# STM32P48.net
KiCad netlist of a schematic drawn in Altium Designer
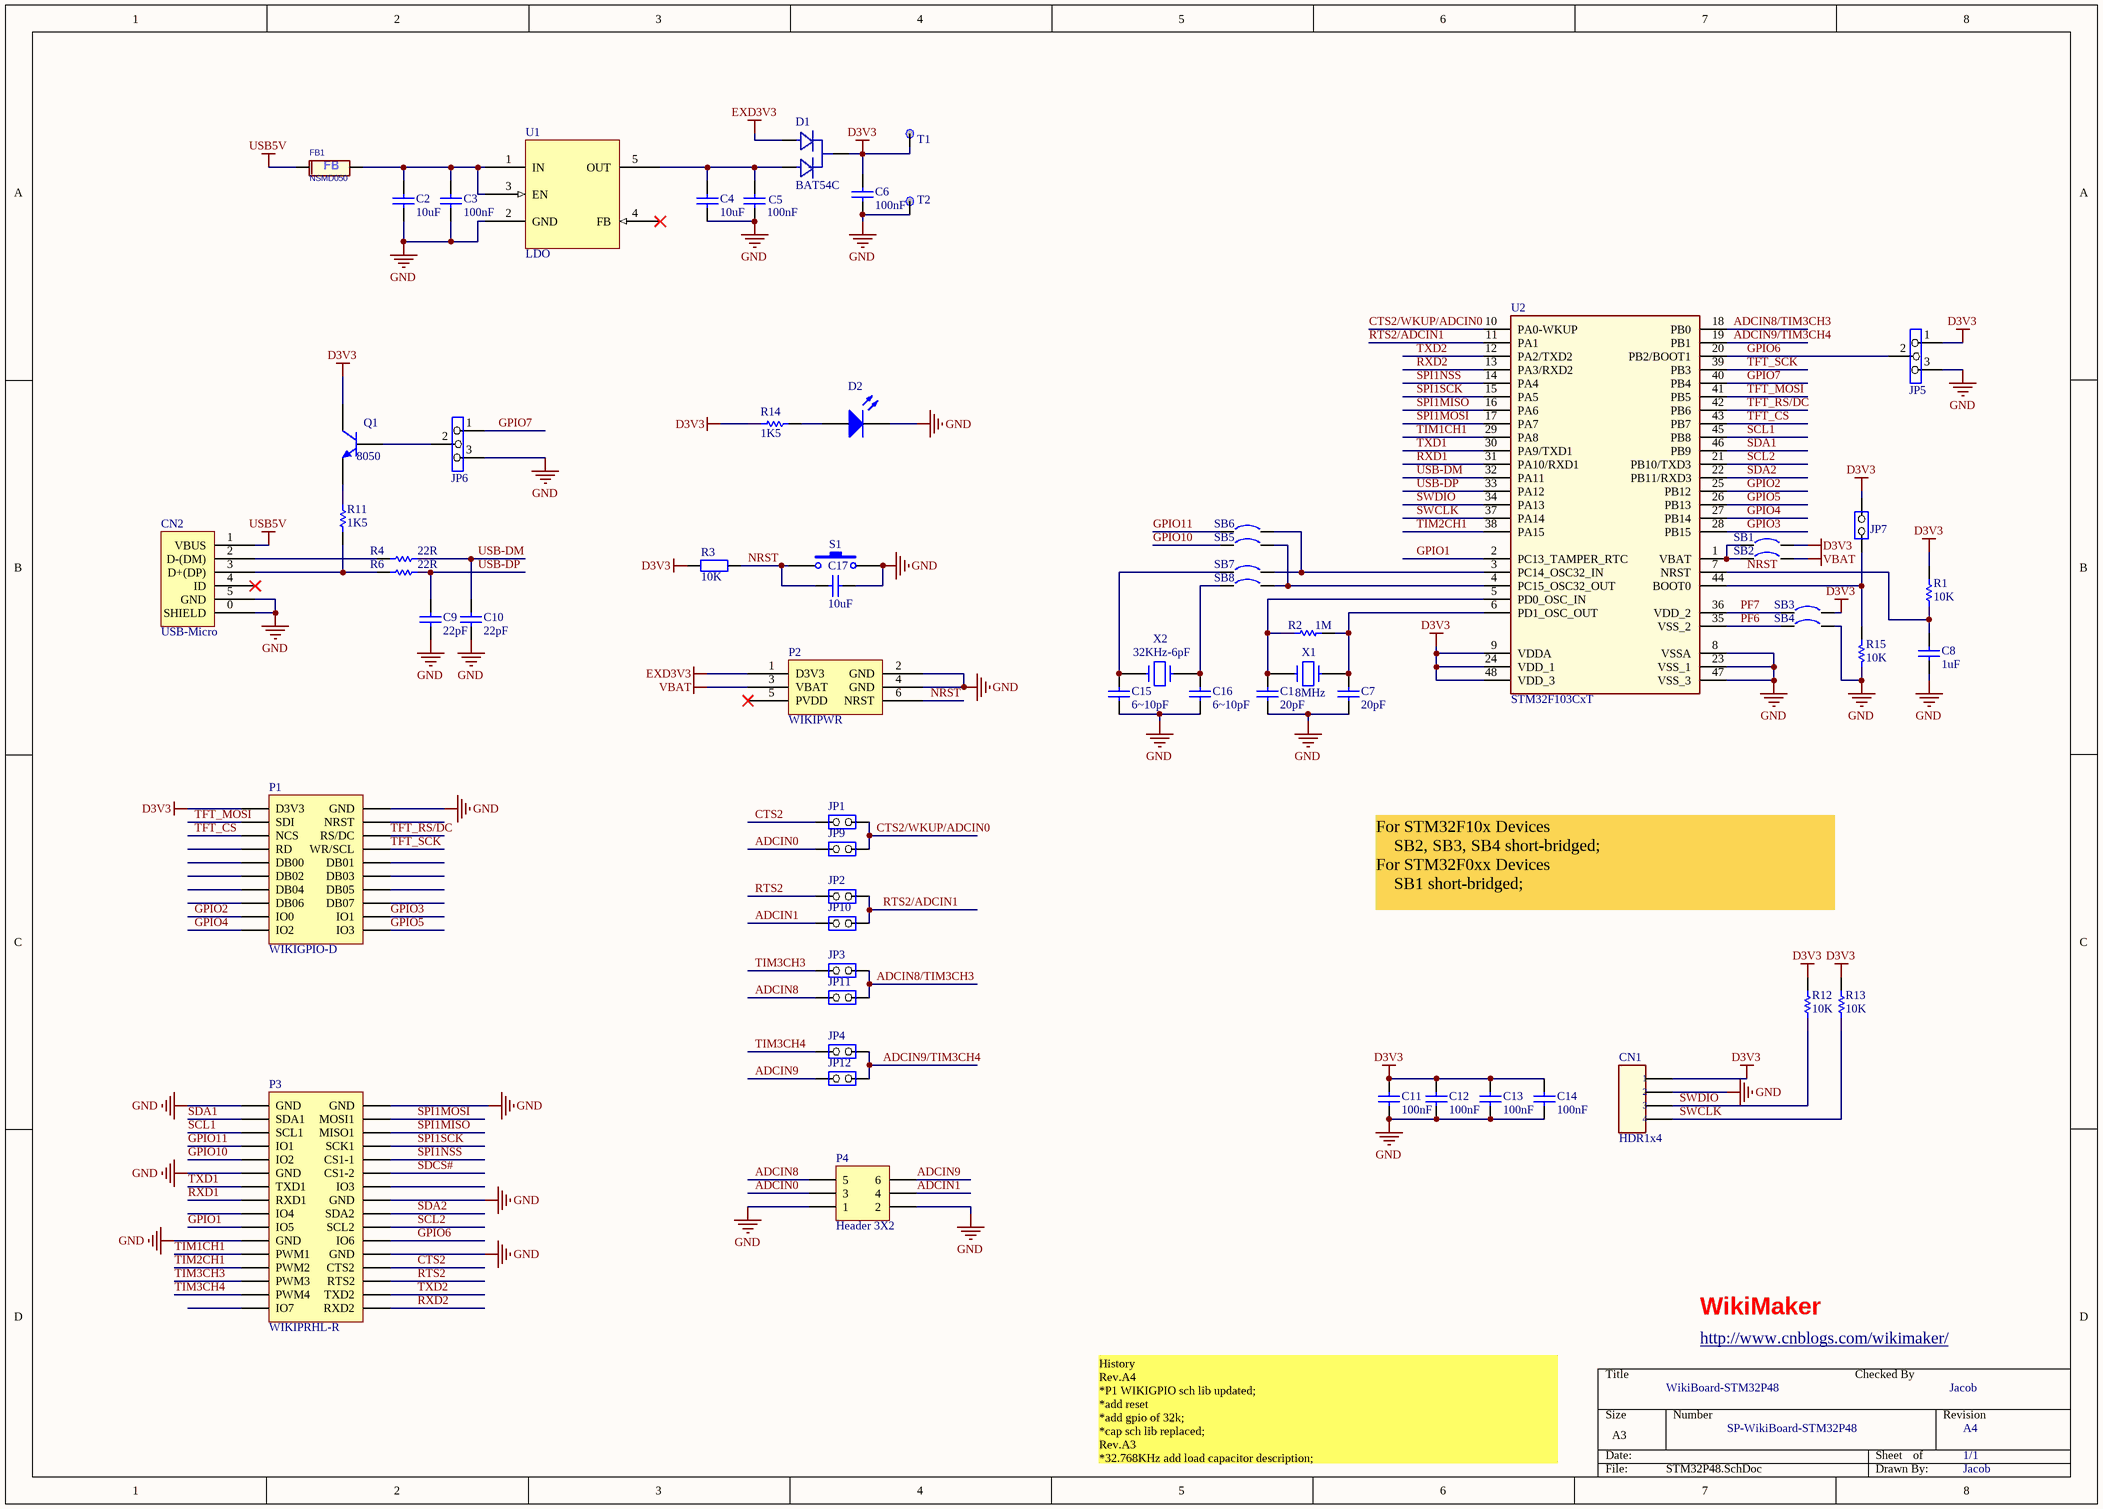
[diagram p0: STM32P48.SchDoc]

(export (version "E")
  (design (tool "Eeschema 10.0.6"))
  (components
    (comp (ref "C1")
      (value "20pF")
      (footprint "C0603L")
      (description "Capacitor")
      (fields (field (name "PUBLISHER") "Altium Limited"))
      (libsource (lib "Miscellaneous Devices") (part "Cap"))
    )
    (comp (ref "C2")
      (value "10uF")
      (footprint "C0805")
      (description "Capacitor")
      (fields (field (name "PUBLISHER") "Altium Limited"))
      (libsource (lib "Miscellaneous Devices") (part "Cap"))
    )
    (comp (ref "C3")
      (value "100nF")
      (footprint "C0603L")
      (description "Capacitor")
      (fields (field (name "PUBLISHER") "Altium Limited"))
      (libsource (lib "Miscellaneous Devices") (part "Cap"))
    )
    (comp (ref "C4")
      (value "10uF")
      (footprint "C0805")
      (description "Capacitor")
      (fields (field (name "PUBLISHER") "Altium Limited"))
      (libsource (lib "Miscellaneous Devices") (part "Cap"))
    )
    (comp (ref "C5")
      (value "100nF")
      (footprint "C0603L")
      (description "Capacitor")
      (fields (field (name "PUBLISHER") "Altium Limited"))
      (libsource (lib "Miscellaneous Devices") (part "Cap"))
    )
    (comp (ref "C6")
      (value "100nF")
      (footprint "C0603L")
      (description "Capacitor")
      (fields (field (name "PUBLISHER") "Altium Limited"))
      (libsource (lib "Miscellaneous Devices") (part "Cap"))
    )
    (comp (ref "C7")
      (value "20pF")
      (footprint "C0603L")
      (description "Capacitor")
      (fields (field (name "PUBLISHER") "Altium Limited"))
      (libsource (lib "Miscellaneous Devices") (part "Cap"))
    )
    (comp (ref "C8")
      (value "1uF")
      (footprint "C0603L")
      (description "Capacitor")
      (fields (field (name "PUBLISHER") "Altium Limited"))
      (libsource (lib "Miscellaneous Devices") (part "Cap"))
    )
    (comp (ref "C9")
      (value "22pF")
      (footprint "C0603L")
      (description "Capacitor")
      (fields (field (name "PUBLISHER") "Altium Limited"))
      (libsource (lib "Miscellaneous Devices") (part "Cap"))
    )
    (comp (ref "C10")
      (value "22pF")
      (footprint "C0603L")
      (description "Capacitor")
      (fields (field (name "PUBLISHER") "Altium Limited"))
      (libsource (lib "Miscellaneous Devices") (part "Cap"))
    )
    (comp (ref "C11")
      (value "100nF")
      (footprint "C0603L")
      (description "Capacitor")
      (fields (field (name "PUBLISHER") "Altium Limited"))
      (libsource (lib "Miscellaneous Devices") (part "Cap"))
    )
    (comp (ref "C12")
      (value "100nF")
      (footprint "C0603L")
      (description "Capacitor")
      (fields (field (name "PUBLISHER") "Altium Limited"))
      (libsource (lib "Miscellaneous Devices") (part "Cap"))
    )
    (comp (ref "C13")
      (value "100nF")
      (footprint "C0603L")
      (description "Capacitor")
      (fields (field (name "PUBLISHER") "Altium Limited"))
      (libsource (lib "Miscellaneous Devices") (part "Cap"))
    )
    (comp (ref "C14")
      (value "100nF")
      (footprint "C0603L")
      (description "Capacitor")
      (fields (field (name "PUBLISHER") "Altium Limited"))
      (libsource (lib "Miscellaneous Devices") (part "Cap"))
    )
    (comp (ref "C15")
      (value "6~10pF")
      (footprint "C0603L")
      (description "Capacitor")
      (fields (field (name "PUBLISHER") "Altium Limited"))
      (libsource (lib "Miscellaneous Devices") (part "Cap"))
    )
    (comp (ref "C16")
      (value "6~10pF")
      (footprint "C0603L")
      (description "Capacitor")
      (fields (field (name "PUBLISHER") "Altium Limited"))
      (libsource (lib "Miscellaneous Devices") (part "Cap"))
    )
    (comp (ref "C17")
      (value "10uF")
      (footprint "C0603L")
      (description "Capacitor")
      (fields (field (name "PUBLISHER") "Altium Limited"))
      (libsource (lib "Miscellaneous Devices") (part "Cap"))
    )
    (comp (ref "CN1") (value "HDR1x4") (footprint "HDR1x4") (libsource (lib "Mylib") (part "CON4")))
    (comp (ref "CN2")
      (value "USB-Micro")
      (footprint "USB-MICRO-Lite")
      (libsource (lib "Connector") (part "USB-Micro"))
    )
    (comp (ref "D1")
      (value "BAT54C")
      (footprint "BAT54C")
      (description "DOUBLE SHOTTKEY DIODES")
      (libsource (lib "Misc") (part "BAT54C"))
    )
    (comp (ref "D2")
      (value "LED1")
      (footprint "0603PN")
      (description "Typical RED GaAs LED")
      (fields (field (name "PUBLISHER") "Altium Limited"))
      (libsource (lib "Misc") (part "LED1"))
    )
    (comp (ref "FB1")
      (value "NSMD050")
      (footprint "R1206")
      (description "Ferrite Beads Inductors Impedance:120Ω±25% Rated Current:1500mA DC Resistance:0.095Ω")
      (fields
        (field (name "MANUFACTURER") "muRata")
        (field (name "MANUFACTURER PART NUMBER") "BLM15EG121SN1")
      )
      (libsource (lib "Mylib") (part "FB"))
    )
    (comp (ref "JP1")
      (value "Jumper2-2")
      (footprint "HDR1X2/2.00MM")
      (description "Jumper2")
      (libsource (lib "Misc") (part "Jumper2-2"))
    )
    (comp (ref "JP2")
      (value "Jumper2-2")
      (footprint "HDR1X2/2.00MM")
      (description "Jumper2")
      (libsource (lib "Misc") (part "Jumper2-2"))
    )
    (comp (ref "JP3")
      (value "Jumper2-2")
      (footprint "HDR1X2/2.00MM")
      (description "Jumper2")
      (libsource (lib "Misc") (part "Jumper2-2"))
    )
    (comp (ref "JP4")
      (value "Jumper2-2")
      (footprint "HDR1X2/2.00MM")
      (description "Jumper2")
      (libsource (lib "Misc") (part "Jumper2-2"))
    )
    (comp (ref "JP5") (value "Jumper3") (footprint "HDR1X3/2.00mm") (libsource (lib "Misc") (part "Jumper3")))
    (comp (ref "JP6") (value "Jumper3") (footprint "HDR1X3/2.00mm") (libsource (lib "Misc") (part "Jumper3")))
    (comp (ref "JP7")
      (value "Jumper2-2")
      (footprint "HDR1X2/2.00MM")
      (description "Jumper2")
      (libsource (lib "Misc") (part "Jumper2-2"))
    )
    (comp (ref "JP9")
      (value "Jumper2-2")
      (footprint "HDR1X2/2.00MM")
      (description "Jumper2")
      (libsource (lib "Misc") (part "Jumper2-2"))
    )
    (comp (ref "JP10")
      (value "Jumper2-2")
      (footprint "HDR1X2/2.00MM")
      (description "Jumper2")
      (libsource (lib "Misc") (part "Jumper2-2"))
    )
    (comp (ref "JP11")
      (value "Jumper2-2")
      (footprint "HDR1X2/2.00MM")
      (description "Jumper2")
      (libsource (lib "Misc") (part "Jumper2-2"))
    )
    (comp (ref "JP12")
      (value "Jumper2-2")
      (footprint "HDR1X2/2.00MM")
      (description "Jumper2")
      (libsource (lib "Misc") (part "Jumper2-2"))
    )
    (comp (ref "P1")
      (value "WIKIGPIO-D")
      (footprint "WIKIGPIO-U")
      (description "Header, 9-Pin, Dual row")
      (fields (field (name "PUBLISHER") "Altium Limited"))
      (libsource (lib "Connector") (part "WIKIGPIO-D"))
    )
    (comp (ref "P2")
      (value "WIKIPWR")
      (footprint "WIKIPWR")
      (description "PWR HDR")
      (libsource (lib "Connector") (part "WIKIPWR"))
    )
    (comp (ref "P3")
      (value "WIKIPRHL-R")
      (footprint "HDR2X16-WIKIPRHL-R")
      (description "Header, 16-Pin, Dual row")
      (fields (field (name "PUBLISHER") "Altium Limited"))
      (libsource (lib "Connector") (part "WIKIPRHL-R"))
    )
    (comp (ref "P4")
      (value "Header 3X2")
      (footprint "HDR2X3/2.54MM")
      (description "Header, 3-Pin, Dual row")
      (fields (field (name "PUBLISHER") "Altium Limited"))
      (libsource (lib "Miscellaneous Connectors") (part "Header 3X2"))
    )
    (comp (ref "Q1")
      (value "8050")
      (footprint "SOT23-3L(123)")
      (description "NPN General Purpose Amplifier")
      (fields (field (name "PUBLISHER") "Altium Limited"))
      (libsource (lib "Misc") (part "8050"))
    )
    (comp (ref "R1")
      (value "10K")
      (footprint "R0603")
      (description "Resistor")
      (libsource (lib "Mylib") (part "RES"))
    )
    (comp (ref "R2")
      (value "1M")
      (footprint "R0603")
      (description "Resistor")
      (libsource (lib "Mylib") (part "RES"))
    )
    (comp (ref "R3")
      (value "10K")
      (footprint "R0603")
      (description "Resistor")
      (fields (field (name "PUBLISHER") "Altium Limited"))
      (libsource (lib "Miscellaneous Devices") (part "Res2"))
    )
    (comp (ref "R4")
      (value "22R")
      (footprint "R0603")
      (description "Resistor")
      (libsource (lib "Mylib") (part "RES"))
    )
    (comp (ref "R6")
      (value "22R")
      (footprint "R0603")
      (description "Resistor")
      (libsource (lib "Mylib") (part "RES"))
    )
    (comp (ref "R11")
      (value "1K5")
      (footprint "R0603")
      (description "Resistor")
      (libsource (lib "Mylib") (part "RES"))
    )
    (comp (ref "R12")
      (value "10K")
      (footprint "R0603")
      (description "Resistor")
      (libsource (lib "Mylib") (part "RES"))
    )
    (comp (ref "R13")
      (value "10K")
      (footprint "R0603")
      (description "Resistor")
      (libsource (lib "Mylib") (part "RES"))
    )
    (comp (ref "R14")
      (value "1K5")
      (footprint "R0603")
      (description "Resistor")
      (libsource (lib "Mylib") (part "RES"))
    )
    (comp (ref "R15")
      (value "10K")
      (footprint "R0603")
      (description "Resistor")
      (libsource (lib "Mylib") (part "RES"))
    )
    (comp (ref "S1")
      (value "~")
      (footprint "KEY-2x4-SMD")
      (description "Switch")
      (fields (field (name "PUBLISHER") "Altium Limited"))
      (libsource (lib "Miscellaneous Devices") (part "SW-PB"))
    )
    (comp (ref "SB1")
      (value "Circuit Breaker")
      (footprint "JP2_SMD")
      (fields (field (name "PUBLISHER") "Altium Limited"))
      (libsource (lib "MB915") (part "Circuit Breaker"))
    )
    (comp (ref "SB2")
      (value "Circuit Breaker")
      (footprint "JP2_SMD")
      (fields (field (name "PUBLISHER") "Altium Limited"))
      (libsource (lib "MB915") (part "Circuit Breaker"))
    )
    (comp (ref "SB3")
      (value "Circuit Breaker")
      (footprint "JP2_SMD")
      (fields (field (name "PUBLISHER") "Altium Limited"))
      (libsource (lib "MB915") (part "Circuit Breaker"))
    )
    (comp (ref "SB4")
      (value "Circuit Breaker")
      (footprint "JP2_SMD")
      (fields (field (name "PUBLISHER") "Altium Limited"))
      (libsource (lib "MB915") (part "Circuit Breaker"))
    )
    (comp (ref "SB5")
      (value "Circuit Breaker")
      (footprint "JP2_SMD")
      (fields (field (name "PUBLISHER") "Altium Limited"))
      (libsource (lib "MB915") (part "Circuit Breaker"))
    )
    (comp (ref "SB6")
      (value "Circuit Breaker")
      (footprint "JP2_SMD")
      (fields (field (name "PUBLISHER") "Altium Limited"))
      (libsource (lib "MB915") (part "Circuit Breaker"))
    )
    (comp (ref "SB7")
      (value "Circuit Breaker")
      (footprint "JP2_SMD")
      (fields (field (name "PUBLISHER") "Altium Limited"))
      (libsource (lib "MB915") (part "Circuit Breaker"))
    )
    (comp (ref "SB8")
      (value "Circuit Breaker")
      (footprint "JP2_SMD")
      (fields (field (name "PUBLISHER") "Altium Limited"))
      (libsource (lib "MB915") (part "Circuit Breaker"))
    )
    (comp (ref "T1")
      (value "TP")
      (footprint "TP")
      (description "Test Point")
      (libsource (lib "Misc") (part "TP"))
    )
    (comp (ref "T2")
      (value "TP")
      (footprint "TP")
      (description "Test Point")
      (libsource (lib "Misc") (part "TP"))
    )
    (comp (ref "U1")
      (value "LDO")
      (footprint "SOT23-5")
      (description "General LDO SOT23-5")
      (libsource (lib "Power") (part "LDO-SOT23-5"))
    )
    (comp (ref "U2")
      (value "STM32F103CxT")
      (footprint "LQFP-48")
      (description "Cortex M3, 48-pin LQFP")
      (libsource (lib "Processor") (part "STM32F103CxT"))
    )
    (comp (ref "X1")
      (value "8MHz")
      (footprint "XTAL_socket")
      (description "Crystal")
      (libsource (lib "*") (part "CRYSTAL"))
    )
    (comp (ref "X2")
      (value "32KHz-6pF")
      (footprint "XTAL0602")
      (description "Crystal")
      (libsource (lib "*") (part "CRYSTAL"))
    )
  )
  (nets
    (net (code "1") (name "/ADCIN0") (class "Default")
      (node (ref "JP9") (pin "1") (pinfunction "COMMON_1") (pintype "passive"))
      (node (ref "P4") (pin "3") (pinfunction "3_3") (pintype "passive"))
    )
    (net (code "2") (name "/ADCIN1") (class "Default")
      (node (ref "JP10") (pin "1") (pinfunction "COMMON_1") (pintype "passive"))
      (node (ref "P4") (pin "4") (pinfunction "4_4") (pintype "passive"))
    )
    (net (code "3") (name "/ADCIN8") (class "Default")
      (node (ref "JP11") (pin "1") (pinfunction "COMMON_1") (pintype "passive"))
      (node (ref "P4") (pin "5") (pinfunction "5_5") (pintype "passive"))
    )
    (net (code "4") (name "/ADCIN8{slash}TIM3CH3") (class "Default")
      (node (ref "JP11") (pin "2") (pinfunction "NO_2") (pintype "passive"))
      (node (ref "JP3") (pin "2") (pinfunction "NO_2") (pintype "passive"))
      (node (ref "U2") (pin "18") (pinfunction "PB0_18") (pintype "passive"))
    )
    (net (code "5") (name "/ADCIN9") (class "Default")
      (node (ref "JP12") (pin "1") (pinfunction "COMMON_1") (pintype "passive"))
      (node (ref "P4") (pin "6") (pinfunction "6_6") (pintype "passive"))
    )
    (net (code "6") (name "/ADCIN9{slash}TIM3CH4") (class "Default")
      (node (ref "JP12") (pin "2") (pinfunction "NO_2") (pintype "passive"))
      (node (ref "JP4") (pin "2") (pinfunction "NO_2") (pintype "passive"))
      (node (ref "U2") (pin "19") (pinfunction "PB1_19") (pintype "passive"))
    )
    (net (code "7") (name "/CTS2") (class "Default")
      (node (ref "JP1") (pin "1") (pinfunction "COMMON_1") (pintype "passive"))
      (node (ref "P3") (pin "26") (pinfunction "CTS2_26") (pintype "passive"))
    )
    (net (code "8") (name "/CTS2{slash}WKUP{slash}ADCIN0") (class "Default")
      (node (ref "JP1") (pin "2") (pinfunction "NO_2") (pintype "passive"))
      (node (ref "JP9") (pin "2") (pinfunction "NO_2") (pintype "passive"))
      (node (ref "U2") (pin "10") (pinfunction "PA0-WKUP_10") (pintype "passive"))
    )
    (net (code "9") (name "/GPIO1") (class "Default")
      (node (ref "P3") (pin "19") (pinfunction "IO5_19") (pintype "passive"))
      (node (ref "U2") (pin "2") (pinfunction "PC13_TAMPER_RTC_2") (pintype "passive"))
    )
    (net (code "10") (name "/GPIO2") (class "Default")
      (node (ref "P1") (pin "17") (pinfunction "IO0_17") (pintype "passive"))
      (node (ref "U2") (pin "25") (pinfunction "PB12_25") (pintype "passive"))
    )
    (net (code "11") (name "/GPIO3") (class "Default")
      (node (ref "P1") (pin "18") (pinfunction "IO1_18") (pintype "passive"))
      (node (ref "U2") (pin "28") (pinfunction "PB15_28") (pintype "passive"))
    )
    (net (code "12") (name "/GPIO4") (class "Default")
      (node (ref "P1") (pin "19") (pinfunction "IO2_19") (pintype "passive"))
      (node (ref "U2") (pin "27") (pinfunction "PB14_27") (pintype "passive"))
    )
    (net (code "13") (name "/GPIO5") (class "Default")
      (node (ref "P1") (pin "20") (pinfunction "IO3_20") (pintype "passive"))
      (node (ref "U2") (pin "26") (pinfunction "PB13_26") (pintype "passive"))
    )
    (net (code "14") (name "/GPIO6") (class "Default")
      (node (ref "JP5") (pin "2") (pintype "passive"))
      (node (ref "P3") (pin "22") (pinfunction "IO6_22") (pintype "passive"))
      (node (ref "U2") (pin "20") (pinfunction "PB2/BOOT1_20") (pintype "passive"))
    )
    (net (code "15") (name "/GPIO7") (class "Default")
      (node (ref "JP6") (pin "1") (pintype "passive"))
      (node (ref "U2") (pin "40") (pinfunction "PB4_40") (pintype "passive"))
    )
    (net (code "16") (name "/GPIO10") (class "Default")
      (node (ref "P3") (pin "9") (pinfunction "IO2_9") (pintype "passive"))
      (node (ref "SB5") (pin "1") (pinfunction "1_1") (pintype "passive"))
    )
    (net (code "17") (name "/GPIO11") (class "Default")
      (node (ref "P3") (pin "7") (pinfunction "IO1_7") (pintype "passive"))
      (node (ref "SB6") (pin "1") (pinfunction "1_1") (pintype "passive"))
    )
    (net (code "18") (name "/NRST") (class "Default")
      (node (ref "C17") (pin "2") (pinfunction "2_2") (pintype "passive"))
      (node (ref "C8") (pin "1") (pinfunction "1_1") (pintype "passive"))
      (node (ref "P2") (pin "6") (pinfunction "NRST_6") (pintype "passive"))
      (node (ref "R1") (pin "1") (pinfunction "1_1") (pintype "passive"))
      (node (ref "R3") (pin "2") (pinfunction "2_2") (pintype "passive"))
      (node (ref "S1") (pin "2") (pinfunction "2_2") (pintype "passive"))
      (node (ref "U2") (pin "7") (pinfunction "NRST_7") (pintype "passive"))
    )
    (net (code "19") (name "/PF6") (class "Default")
      (node (ref "SB4") (pin "1") (pinfunction "1_1") (pintype "passive"))
      (node (ref "U2") (pin "35") (pinfunction "VSS_2_35") (pintype "passive"))
    )
    (net (code "20") (name "/PF7") (class "Default")
      (node (ref "SB3") (pin "1") (pinfunction "1_1") (pintype "passive"))
      (node (ref "U2") (pin "36") (pinfunction "VDD_2_36") (pintype "passive"))
    )
    (net (code "21") (name "/RTS2") (class "Default")
      (node (ref "JP2") (pin "1") (pinfunction "COMMON_1") (pintype "passive"))
      (node (ref "P3") (pin "28") (pinfunction "RTS2_28") (pintype "passive"))
    )
    (net (code "22") (name "/RTS2{slash}ADCIN1") (class "Default")
      (node (ref "JP10") (pin "2") (pinfunction "NO_2") (pintype "passive"))
      (node (ref "JP2") (pin "2") (pinfunction "NO_2") (pintype "passive"))
      (node (ref "U2") (pin "11") (pinfunction "PA1_11") (pintype "passive"))
    )
    (net (code "23") (name "/RXD1") (class "Default")
      (node (ref "P3") (pin "15") (pinfunction "RXD1_15") (pintype "passive"))
      (node (ref "U2") (pin "31") (pinfunction "PA10/RXD1_31") (pintype "passive"))
    )
    (net (code "24") (name "/RXD2") (class "Default")
      (node (ref "P3") (pin "32") (pinfunction "RXD2_32") (pintype "passive"))
      (node (ref "U2") (pin "13") (pinfunction "PA3/RXD2_13") (pintype "passive"))
    )
    (net (code "25") (name "/SCL1") (class "Default")
      (node (ref "P3") (pin "5") (pinfunction "SCL1_5") (pintype "passive"))
      (node (ref "U2") (pin "45") (pinfunction "PB8_45") (pintype "passive"))
    )
    (net (code "26") (name "/SCL2") (class "Default")
      (node (ref "P3") (pin "20") (pinfunction "SCL2_20") (pintype "passive"))
      (node (ref "U2") (pin "21") (pinfunction "PB10/TXD3_21") (pintype "passive"))
    )
    (net (code "27") (name "/SDA1") (class "Default")
      (node (ref "P3") (pin "3") (pinfunction "SDA1_3") (pintype "passive"))
      (node (ref "U2") (pin "46") (pinfunction "PB9_46") (pintype "passive"))
    )
    (net (code "28") (name "/SDA2") (class "Default")
      (node (ref "P3") (pin "18") (pinfunction "SDA2_18") (pintype "passive"))
      (node (ref "U2") (pin "22") (pinfunction "PB11/RXD3_22") (pintype "passive"))
    )
    (net (code "29") (name "/SDCS#") (class "Default")
      (node (ref "P3") (pin "12") (pinfunction "CS1-2_12") (pintype "passive"))
    )
    (net (code "30") (name "/SPI1MISO") (class "Default")
      (node (ref "P3") (pin "6") (pinfunction "MISO1_6") (pintype "passive"))
      (node (ref "U2") (pin "16") (pinfunction "PA6_16") (pintype "passive"))
    )
    (net (code "31") (name "/SPI1MOSI") (class "Default")
      (node (ref "P3") (pin "4") (pinfunction "MOSI1_4") (pintype "passive"))
      (node (ref "U2") (pin "17") (pinfunction "PA7_17") (pintype "passive"))
    )
    (net (code "32") (name "/SPI1NSS") (class "Default")
      (node (ref "P3") (pin "10") (pinfunction "CS1-1_10") (pintype "passive"))
      (node (ref "U2") (pin "14") (pinfunction "PA4_14") (pintype "passive"))
    )
    (net (code "33") (name "/SPI1SCK") (class "Default")
      (node (ref "P3") (pin "8") (pinfunction "SCK1_8") (pintype "passive"))
      (node (ref "U2") (pin "15") (pinfunction "PA5_15") (pintype "passive"))
    )
    (net (code "34") (name "/SWCLK") (class "Default")
      (node (ref "CN1") (pin "4") (pinfunction "4_4") (pintype "passive"))
      (node (ref "R13") (pin "1") (pinfunction "1_1") (pintype "passive"))
      (node (ref "U2") (pin "37") (pinfunction "PA14_37") (pintype "passive"))
    )
    (net (code "35") (name "/SWDIO") (class "Default")
      (node (ref "CN1") (pin "3") (pinfunction "3_3") (pintype "passive"))
      (node (ref "R12") (pin "1") (pinfunction "1_1") (pintype "passive"))
      (node (ref "U2") (pin "34") (pinfunction "PA13_34") (pintype "passive"))
    )
    (net (code "36") (name "/TFT_CS") (class "Default")
      (node (ref "P1") (pin "5") (pinfunction "NCS_5") (pintype "passive"))
      (node (ref "U2") (pin "43") (pinfunction "PB7_43") (pintype "passive"))
    )
    (net (code "37") (name "/TFT_MOSI") (class "Default")
      (node (ref "P1") (pin "3") (pinfunction "SDI_3") (pintype "passive"))
      (node (ref "U2") (pin "41") (pinfunction "PB5_41") (pintype "passive"))
    )
    (net (code "38") (name "/TFT_RS{slash}DC") (class "Default")
      (node (ref "P1") (pin "6") (pinfunction "RS/DC_6") (pintype "passive"))
      (node (ref "U2") (pin "42") (pinfunction "PB6_42") (pintype "passive"))
    )
    (net (code "39") (name "/TFT_SCK") (class "Default")
      (node (ref "P1") (pin "8") (pinfunction "WR/SCL_8") (pintype "passive"))
      (node (ref "U2") (pin "39") (pinfunction "PB3_39") (pintype "passive"))
    )
    (net (code "40") (name "/TIM1CH1") (class "Default")
      (node (ref "P3") (pin "23") (pinfunction "PWM1_23") (pintype "passive"))
      (node (ref "U2") (pin "29") (pinfunction "PA8_29") (pintype "passive"))
    )
    (net (code "41") (name "/TIM2CH1") (class "Default")
      (node (ref "P3") (pin "25") (pinfunction "PWM2_25") (pintype "passive"))
      (node (ref "U2") (pin "38") (pinfunction "PA15_38") (pintype "passive"))
    )
    (net (code "42") (name "/TIM3CH3") (class "Default")
      (node (ref "JP3") (pin "1") (pinfunction "COMMON_1") (pintype "passive"))
      (node (ref "P3") (pin "27") (pinfunction "PWM3_27") (pintype "passive"))
    )
    (net (code "43") (name "/TIM3CH4") (class "Default")
      (node (ref "JP4") (pin "1") (pinfunction "COMMON_1") (pintype "passive"))
      (node (ref "P3") (pin "29") (pinfunction "PWM4_29") (pintype "passive"))
    )
    (net (code "44") (name "/TXD1") (class "Default")
      (node (ref "P3") (pin "13") (pinfunction "TXD1_13") (pintype "passive"))
      (node (ref "U2") (pin "30") (pinfunction "PA9/TXD1_30") (pintype "passive"))
    )
    (net (code "45") (name "/TXD2") (class "Default")
      (node (ref "P3") (pin "30") (pinfunction "TXD2_30") (pintype "passive"))
      (node (ref "U2") (pin "12") (pinfunction "PA2/TXD2_12") (pintype "passive"))
    )
    (net (code "46") (name "/USB-DM") (class "Default")
      (node (ref "C10") (pin "1") (pinfunction "1_1") (pintype "passive"))
      (node (ref "R4") (pin "1") (pinfunction "1_1") (pintype "passive"))
      (node (ref "U2") (pin "32") (pinfunction "PA11_32") (pintype "passive"))
    )
    (net (code "47") (name "/USB-DP") (class "Default")
      (node (ref "C9") (pin "1") (pinfunction "1_1") (pintype "passive"))
      (node (ref "R6") (pin "1") (pinfunction "1_1") (pintype "passive"))
      (node (ref "U2") (pin "33") (pinfunction "PA12_33") (pintype "passive"))
    )
    (net (code "48") (name "D3V3") (class "Default")
      (node (ref "C11") (pin "1") (pinfunction "1_1") (pintype "passive"))
      (node (ref "C12") (pin "1") (pinfunction "1_1") (pintype "passive"))
      (node (ref "C13") (pin "1") (pinfunction "1_1") (pintype "passive"))
      (node (ref "C14") (pin "1") (pinfunction "1_1") (pintype "passive"))
      (node (ref "C6") (pin "1") (pinfunction "1_1") (pintype "passive"))
      (node (ref "CN1") (pin "1") (pinfunction "1_1") (pintype "passive"))
      (node (ref "D1") (pin "3") (pinfunction "3_3") (pintype "passive"))
      (node (ref "JP5") (pin "1") (pintype "passive"))
      (node (ref "JP7") (pin "2") (pinfunction "NO_2") (pintype "passive"))
      (node (ref "P1") (pin "1") (pinfunction "D3V3_1") (pintype "passive"))
      (node (ref "Q1") (pin "3") (pinfunction "C_3") (pintype "passive"))
      (node (ref "R1") (pin "2") (pinfunction "2_2") (pintype "passive"))
      (node (ref "R12") (pin "2") (pinfunction "2_2") (pintype "passive"))
      (node (ref "R13") (pin "2") (pinfunction "2_2") (pintype "passive"))
      (node (ref "R14") (pin "1") (pinfunction "1_1") (pintype "passive"))
      (node (ref "R3") (pin "1") (pinfunction "1_1") (pintype "passive"))
      (node (ref "SB1") (pin "2") (pinfunction "2_2") (pintype "passive"))
      (node (ref "SB3") (pin "2") (pinfunction "2_2") (pintype "passive"))
      (node (ref "T1") (pin "1") (pinfunction "1_1") (pintype "passive"))
      (node (ref "U2") (pin "24") (pinfunction "VDD_1_24") (pintype "passive"))
      (node (ref "U2") (pin "48") (pinfunction "VDD_3_48") (pintype "passive"))
      (node (ref "U2") (pin "9") (pinfunction "VDDA_9") (pintype "passive"))
    )
    (net (code "49") (name "EXD3V3") (class "Default")
      (node (ref "D1") (pin "2") (pintype "passive"))
      (node (ref "P2") (pin "1") (pinfunction "D3V3_1") (pintype "passive"))
    )
    (net (code "50") (name "GND") (class "Default")
      (node (ref "C1") (pin "2") (pinfunction "2_2") (pintype "passive"))
      (node (ref "C10") (pin "2") (pinfunction "2_2") (pintype "passive"))
      (node (ref "C11") (pin "2") (pinfunction "2_2") (pintype "passive"))
      (node (ref "C12") (pin "2") (pinfunction "2_2") (pintype "passive"))
      (node (ref "C13") (pin "2") (pinfunction "2_2") (pintype "passive"))
      (node (ref "C14") (pin "2") (pinfunction "2_2") (pintype "passive"))
      (node (ref "C15") (pin "2") (pinfunction "2_2") (pintype "passive"))
      (node (ref "C16") (pin "2") (pinfunction "2_2") (pintype "passive"))
      (node (ref "C17") (pin "1") (pinfunction "1_1") (pintype "passive"))
      (node (ref "C2") (pin "2") (pinfunction "2_2") (pintype "passive"))
      (node (ref "C3") (pin "2") (pinfunction "2_2") (pintype "passive"))
      (node (ref "C4") (pin "2") (pinfunction "2_2") (pintype "passive"))
      (node (ref "C5") (pin "2") (pinfunction "2_2") (pintype "passive"))
      (node (ref "C6") (pin "2") (pinfunction "2_2") (pintype "passive"))
      (node (ref "C7") (pin "2") (pinfunction "2_2") (pintype "passive"))
      (node (ref "C8") (pin "2") (pinfunction "2_2") (pintype "passive"))
      (node (ref "C9") (pin "2") (pinfunction "2_2") (pintype "passive"))
      (node (ref "CN1") (pin "2") (pinfunction "2_2") (pintype "passive"))
      (node (ref "CN2") (pin "0") (pinfunction "SHIELD_0") (pintype "passive"))
      (node (ref "CN2") (pin "5") (pinfunction "GND_5") (pintype "passive"))
      (node (ref "D2") (pin "2") (pinfunction "K_2") (pintype "passive"))
      (node (ref "JP5") (pin "3") (pintype "passive"))
      (node (ref "JP6") (pin "3") (pintype "passive"))
      (node (ref "P1") (pin "2") (pinfunction "GND_2") (pintype "passive"))
      (node (ref "P2") (pin "2") (pinfunction "GND_2") (pintype "passive"))
      (node (ref "P2") (pin "4") (pinfunction "GND_4") (pintype "passive"))
      (node (ref "P3") (pin "1") (pinfunction "GND_1") (pintype "passive"))
      (node (ref "P3") (pin "11") (pinfunction "GND_11") (pintype "passive"))
      (node (ref "P3") (pin "16") (pinfunction "GND_16") (pintype "passive"))
      (node (ref "P3") (pin "2") (pinfunction "GND_2") (pintype "passive"))
      (node (ref "P3") (pin "21") (pinfunction "GND_21") (pintype "passive"))
      (node (ref "P3") (pin "24") (pinfunction "GND_24") (pintype "passive"))
      (node (ref "P4") (pin "1") (pinfunction "1_1") (pintype "passive"))
      (node (ref "P4") (pin "2") (pinfunction "2_2") (pintype "passive"))
      (node (ref "R15") (pin "1") (pinfunction "1_1") (pintype "passive"))
      (node (ref "S1") (pin "1") (pinfunction "1_1") (pintype "passive"))
      (node (ref "SB4") (pin "2") (pinfunction "2_2") (pintype "passive"))
      (node (ref "T2") (pin "1") (pinfunction "1_1") (pintype "passive"))
      (node (ref "U1") (pin "2") (pinfunction "GND_2") (pintype "power_in"))
      (node (ref "U2") (pin "23") (pinfunction "VSS_1_23") (pintype "passive"))
      (node (ref "U2") (pin "47") (pinfunction "VSS_3_47") (pintype "passive"))
      (node (ref "U2") (pin "8") (pinfunction "VSSA_8") (pintype "passive"))
    )
    (net (code "51") (name "Net-(C15-Pad1)") (class "Default")
      (node (ref "C15") (pin "1") (pinfunction "1_1") (pintype "passive"))
      (node (ref "SB7") (pin "1") (pinfunction "1_1") (pintype "passive"))
      (node (ref "X2") (pin "2") (pinfunction "2_2") (pintype "passive"))
    )
    (net (code "52") (name "Net-(C16-Pad1)") (class "Default")
      (node (ref "C16") (pin "1") (pinfunction "1_1") (pintype "passive"))
      (node (ref "SB8") (pin "1") (pinfunction "1_1") (pintype "passive"))
      (node (ref "X2") (pin "1") (pinfunction "1_1") (pintype "passive"))
    )
    (net (code "53") (name "Net-(CN2-D+(DP))") (class "Default")
      (node (ref "CN2") (pin "3") (pinfunction "D+(DP)_3") (pintype "passive"))
      (node (ref "R11") (pin "2") (pinfunction "2_2") (pintype "passive"))
      (node (ref "R6") (pin "2") (pinfunction "2_2") (pintype "passive"))
    )
    (net (code "54") (name "Net-(CN2-D-(DM))") (class "Default")
      (node (ref "CN2") (pin "2") (pinfunction "D-(DM)_2") (pintype "passive"))
      (node (ref "R4") (pin "2") (pinfunction "2_2") (pintype "passive"))
    )
    (net (code "55") (name "Net-(D2-A)") (class "Default")
      (node (ref "D2") (pin "1") (pinfunction "A_1") (pintype "passive"))
      (node (ref "R14") (pin "2") (pinfunction "2_2") (pintype "passive"))
    )
    (net (code "56") (name "Net-(JP7-COMMON)") (class "Default")
      (node (ref "JP7") (pin "1") (pinfunction "COMMON_1") (pintype "passive"))
      (node (ref "R15") (pin "2") (pinfunction "2_2") (pintype "passive"))
      (node (ref "U2") (pin "44") (pinfunction "BOOT0_44") (pintype "passive"))
    )
    (net (code "57") (name "Net-(Q1-B)") (class "Default")
      (node (ref "JP6") (pin "2") (pintype "passive"))
      (node (ref "Q1") (pin "1") (pinfunction "B_1") (pintype "passive"))
    )
    (net (code "58") (name "Net-(Q1-E)") (class "Default")
      (node (ref "Q1") (pin "2") (pinfunction "E_2") (pintype "passive"))
      (node (ref "R11") (pin "1") (pinfunction "1_1") (pintype "passive"))
    )
    (net (code "59") (name "Net-(U1-EN)") (class "Default")
      (node (ref "C2") (pin "1") (pinfunction "1_1") (pintype "passive"))
      (node (ref "C3") (pin "1") (pinfunction "1_1") (pintype "passive"))
      (node (ref "FB1") (pin "2") (pinfunction "2_2") (pintype "passive"))
      (node (ref "U1") (pin "1") (pinfunction "IN_1") (pintype "power_in"))
      (node (ref "U1") (pin "3") (pinfunction "EN_3") (pintype "input"))
    )
    (net (code "60") (name "Net-(U1-OUT)") (class "Default")
      (node (ref "C4") (pin "1") (pinfunction "1_1") (pintype "passive"))
      (node (ref "C5") (pin "1") (pinfunction "1_1") (pintype "passive"))
      (node (ref "D1") (pin "1") (pintype "passive"))
      (node (ref "U1") (pin "5") (pinfunction "OUT_5") (pintype "power_in"))
    )
    (net (code "61") (name "Net-(U2-PC14_OSC32_IN)") (class "Default")
      (node (ref "SB6") (pin "2") (pinfunction "2_2") (pintype "passive"))
      (node (ref "SB7") (pin "2") (pinfunction "2_2") (pintype "passive"))
      (node (ref "U2") (pin "3") (pinfunction "PC14_OSC32_IN_3") (pintype "passive"))
    )
    (net (code "62") (name "Net-(U2-PC15_OSC32_OUT)") (class "Default")
      (node (ref "SB5") (pin "2") (pinfunction "2_2") (pintype "passive"))
      (node (ref "SB8") (pin "2") (pinfunction "2_2") (pintype "passive"))
      (node (ref "U2") (pin "4") (pinfunction "PC15_OSC32_OUT_4") (pintype "passive"))
    )
    (net (code "63") (name "Net-(U2-PD0_OSC_IN)") (class "Default")
      (node (ref "C1") (pin "1") (pinfunction "1_1") (pintype "passive"))
      (node (ref "R2") (pin "1") (pinfunction "1_1") (pintype "passive"))
      (node (ref "U2") (pin "5") (pinfunction "PD0_OSC_IN_5") (pintype "passive"))
      (node (ref "X1") (pin "2") (pinfunction "2_2") (pintype "passive"))
    )
    (net (code "64") (name "Net-(U2-PD1_OSC_OUT)") (class "Default")
      (node (ref "C7") (pin "1") (pinfunction "1_1") (pintype "passive"))
      (node (ref "R2") (pin "2") (pinfunction "2_2") (pintype "passive"))
      (node (ref "U2") (pin "6") (pinfunction "PD1_OSC_OUT_6") (pintype "passive"))
      (node (ref "X1") (pin "1") (pinfunction "1_1") (pintype "passive"))
    )
    (net (code "65") (name "Net-(U2-VBAT)") (class "Default")
      (node (ref "SB1") (pin "1") (pinfunction "1_1") (pintype "passive"))
      (node (ref "SB2") (pin "1") (pinfunction "1_1") (pintype "passive"))
      (node (ref "U2") (pin "1") (pinfunction "VBAT_1") (pintype "passive"))
    )
    (net (code "66") (name "USB5V") (class "Default")
      (node (ref "CN2") (pin "1") (pinfunction "VBUS_1") (pintype "passive"))
      (node (ref "FB1") (pin "1") (pinfunction "1_1") (pintype "passive"))
    )
    (net (code "67") (name "VBAT") (class "Default")
      (node (ref "P2") (pin "3") (pinfunction "VBAT_3") (pintype "passive"))
      (node (ref "SB2") (pin "2") (pinfunction "2_2") (pintype "passive"))
    )
    (net (code "68") (name "unconnected-(CN2-ID-Pad4)") (class "Default")
      (node (ref "CN2") (pin "4") (pinfunction "ID_4") (pintype "passive+no_connect"))
    )
    (net (code "69") (name "unconnected-(P1-DB00-Pad9)") (class "Default")
      (node (ref "P1") (pin "9") (pinfunction "DB00_9") (pintype "passive"))
    )
    (net (code "70") (name "unconnected-(P1-DB01-Pad10)") (class "Default")
      (node (ref "P1") (pin "10") (pinfunction "DB01_10") (pintype "passive"))
    )
    (net (code "71") (name "unconnected-(P1-DB02-Pad11)") (class "Default")
      (node (ref "P1") (pin "11") (pinfunction "DB02_11") (pintype "passive"))
    )
    (net (code "72") (name "unconnected-(P1-DB03-Pad12)") (class "Default")
      (node (ref "P1") (pin "12") (pinfunction "DB03_12") (pintype "passive"))
    )
    (net (code "73") (name "unconnected-(P1-DB04-Pad13)") (class "Default")
      (node (ref "P1") (pin "13") (pinfunction "DB04_13") (pintype "passive"))
    )
    (net (code "74") (name "unconnected-(P1-DB05-Pad14)") (class "Default")
      (node (ref "P1") (pin "14") (pinfunction "DB05_14") (pintype "passive"))
    )
    (net (code "75") (name "unconnected-(P1-DB06-Pad15)") (class "Default")
      (node (ref "P1") (pin "15") (pinfunction "DB06_15") (pintype "passive"))
    )
    (net (code "76") (name "unconnected-(P1-DB07-Pad16)") (class "Default")
      (node (ref "P1") (pin "16") (pinfunction "DB07_16") (pintype "passive"))
    )
    (net (code "77") (name "unconnected-(P1-NRST-Pad4)") (class "Default")
      (node (ref "P1") (pin "4") (pinfunction "NRST_4") (pintype "passive"))
    )
    (net (code "78") (name "unconnected-(P1-RD-Pad7)") (class "Default")
      (node (ref "P1") (pin "7") (pinfunction "RD_7") (pintype "passive"))
    )
    (net (code "79") (name "unconnected-(P2-PVDD-Pad5)") (class "Default")
      (node (ref "P2") (pin "5") (pinfunction "PVDD_5") (pintype "passive+no_connect"))
    )
    (net (code "80") (name "unconnected-(P3-IO3-Pad14)") (class "Default")
      (node (ref "P3") (pin "14") (pinfunction "IO3_14") (pintype "passive"))
    )
    (net (code "81") (name "unconnected-(P3-IO4-Pad17)") (class "Default")
      (node (ref "P3") (pin "17") (pinfunction "IO4_17") (pintype "passive"))
    )
    (net (code "82") (name "unconnected-(P3-IO7-Pad31)") (class "Default")
      (node (ref "P3") (pin "31") (pinfunction "IO7_31") (pintype "passive"))
    )
    (net (code "83") (name "unconnected-(U1-FB-Pad4)") (class "Default")
      (node (ref "U1") (pin "4") (pinfunction "FB_4") (pintype "input+no_connect"))
    )
  )
)
